# I2C-8574-cTc.net
KiCad netlist of a schematic drawn in EAGLE
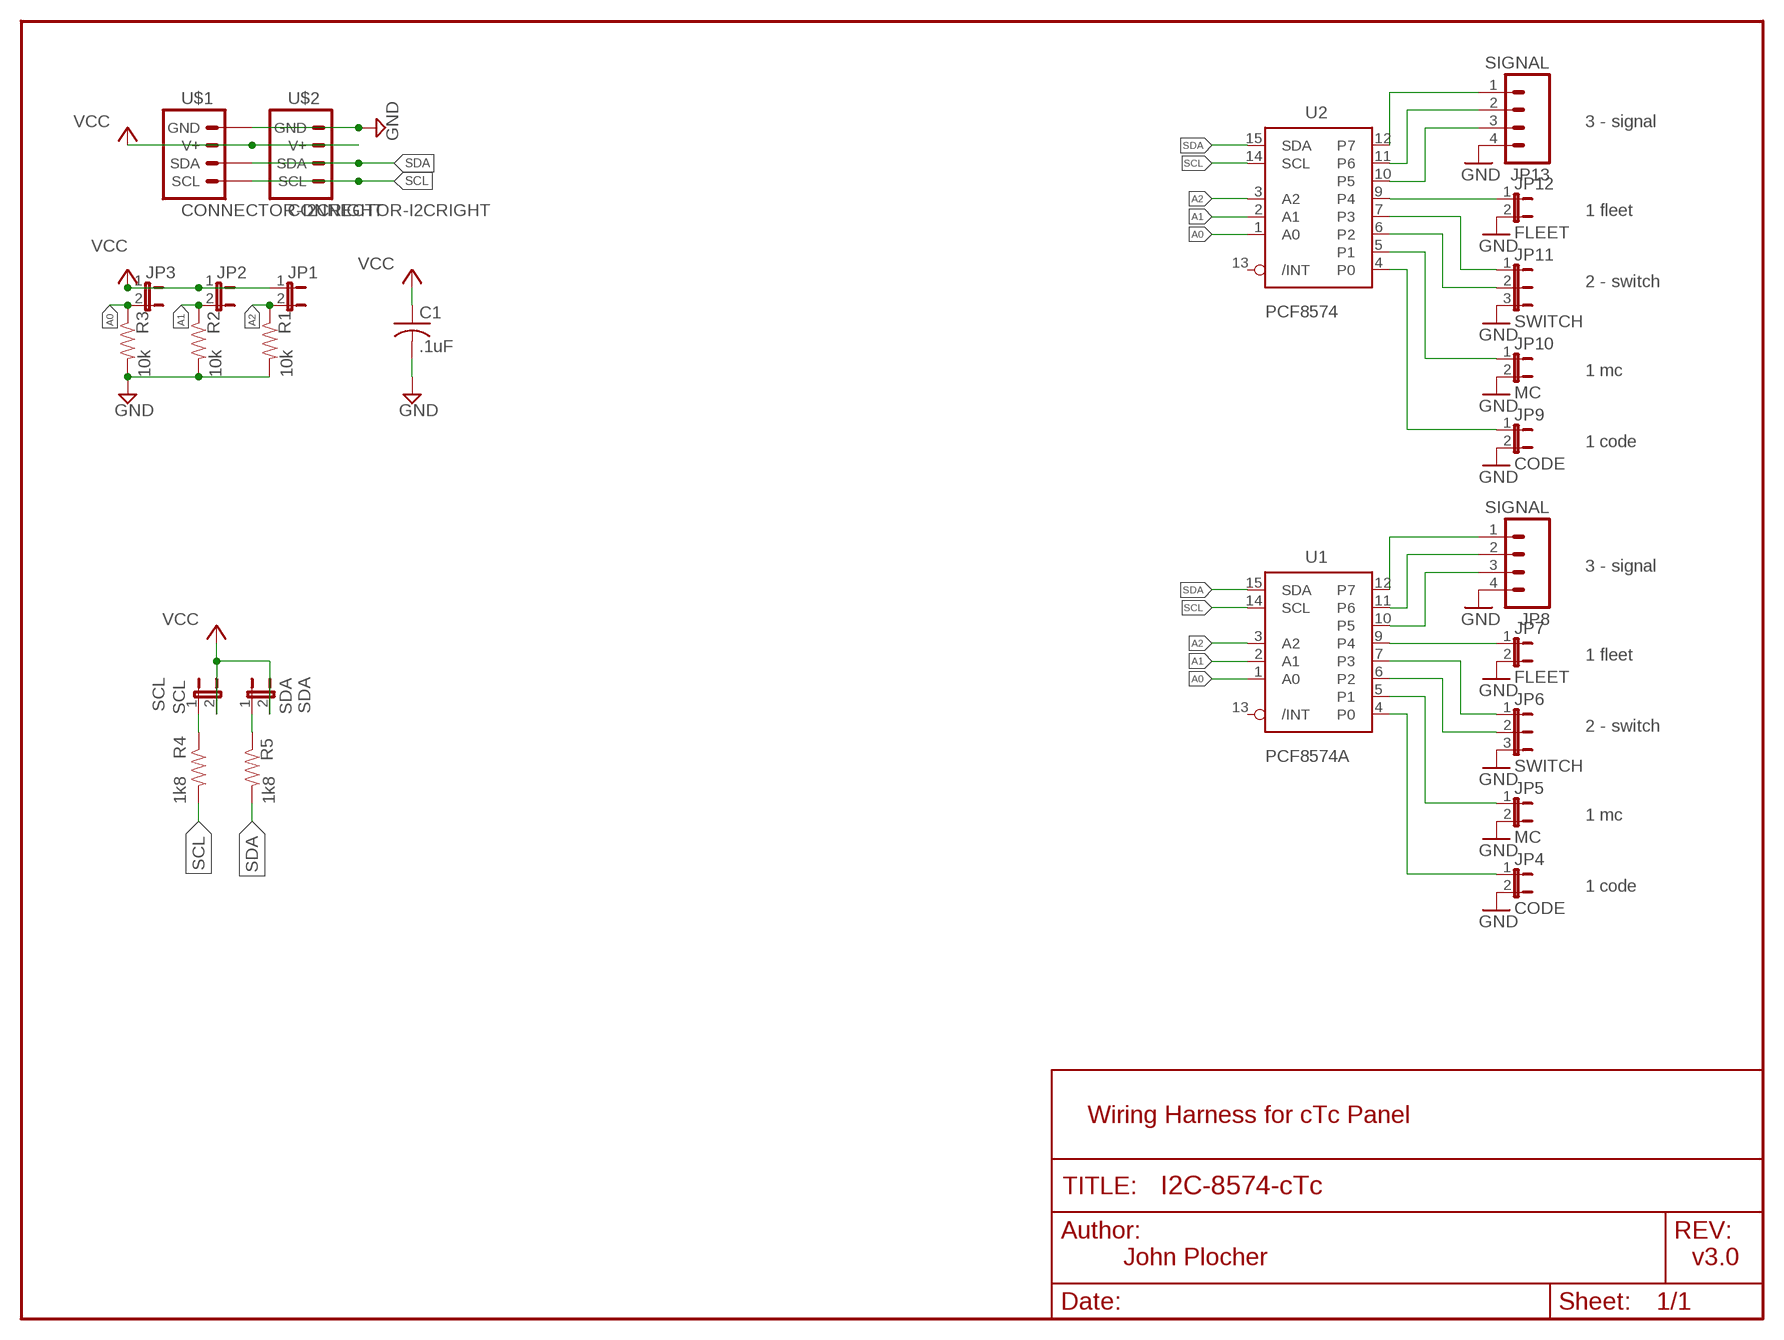
[diagram p0: schematic, sheet 1]

(export (version "E")
  (design (tool "Eeschema 10.0.6"))
  (components
    (comp (ref "C1")
      (value ".1uF")
      (footprint "eagle-import:0805-CAP")
      (libsource (lib "eagle-import") (part "CAP0805"))
    )
    (comp (ref "JP1")
      (value "JUMPER-2SMD-NO")
      (footprint "eagle-import:SJ_2S-NO")
      (libsource (lib "eagle-import") (part "JUMPER-2SMD-NO"))
    )
    (comp (ref "JP2")
      (value "JUMPER-2SMD-NO")
      (footprint "eagle-import:SJ_2S-NO")
      (libsource (lib "eagle-import") (part "JUMPER-2SMD-NO"))
    )
    (comp (ref "JP3")
      (value "JUMPER-2SMD-NO")
      (footprint "eagle-import:SJ_2S-NO")
      (libsource (lib "eagle-import") (part "JUMPER-2SMD-NO"))
    )
    (comp (ref "JP4")
      (value "CODE")
      (footprint "eagle-import:1X02_LOCK")
      (libsource (lib "eagle-import") (part "JUMPER-2PTH_LOCK"))
    )
    (comp (ref "JP5")
      (value "MC")
      (footprint "eagle-import:1X02_LOCK")
      (libsource (lib "eagle-import") (part "JUMPER-2PTH_LOCK"))
    )
    (comp (ref "JP6")
      (value "SWITCH")
      (footprint "eagle-import:1X03")
      (libsource (lib "eagle-import") (part "JUMPER-3PTH-LOCK"))
    )
    (comp (ref "JP7")
      (value "FLEET")
      (footprint "eagle-import:1X02_LOCK")
      (libsource (lib "eagle-import") (part "JUMPER-2PTH_LOCK"))
    )
    (comp (ref "JP8")
      (value "SIGNAL")
      (footprint "eagle-import:1X04_LOCK")
      (libsource (lib "eagle-import") (part "CONNECTOR-M04LOCK"))
    )
    (comp (ref "JP9")
      (value "CODE")
      (footprint "eagle-import:1X02_LOCK")
      (libsource (lib "eagle-import") (part "JUMPER-2PTH_LOCK"))
    )
    (comp (ref "JP10")
      (value "MC")
      (footprint "eagle-import:1X02_LOCK")
      (libsource (lib "eagle-import") (part "JUMPER-2PTH_LOCK"))
    )
    (comp (ref "JP11")
      (value "SWITCH")
      (footprint "eagle-import:1X03")
      (libsource (lib "eagle-import") (part "JUMPER-3PTH-LOCK"))
    )
    (comp (ref "JP12")
      (value "FLEET")
      (footprint "eagle-import:1X02_LOCK")
      (libsource (lib "eagle-import") (part "JUMPER-2PTH_LOCK"))
    )
    (comp (ref "JP13")
      (value "SIGNAL")
      (footprint "eagle-import:1X04_LOCK")
      (libsource (lib "eagle-import") (part "CONNECTOR-M04LOCK"))
    )
    (comp (ref "R1")
      (value "10k")
      (footprint "eagle-import:0805-RES")
      (libsource (lib "eagle-import") (part "R0805-RES"))
    )
    (comp (ref "R2")
      (value "10k")
      (footprint "eagle-import:0805-RES")
      (libsource (lib "eagle-import") (part "R0805-RES"))
    )
    (comp (ref "R3")
      (value "10k")
      (footprint "eagle-import:0805-RES")
      (libsource (lib "eagle-import") (part "R0805-RES"))
    )
    (comp (ref "R4")
      (value "1k8")
      (footprint "eagle-import:0805-RES")
      (libsource (lib "eagle-import") (part "R0805-RES"))
    )
    (comp (ref "R5")
      (value "1k8")
      (footprint "eagle-import:0805-RES")
      (libsource (lib "eagle-import") (part "R0805-RES"))
    )
    (comp (ref "SCL")
      (value "SCL")
      (footprint "eagle-import:1X02_LOCK")
      (libsource (lib "eagle-import") (part "JUMPER-2PTH_LOCK"))
    )
    (comp (ref "SDA")
      (value "SDA")
      (footprint "eagle-import:1X02_LOCK")
      (libsource (lib "eagle-import") (part "JUMPER-2PTH_LOCK"))
    )
    (comp (ref "U$1")
      (value "CONNECTOR-I2CRIGHT")
      (footprint "eagle-import:I2C-R")
      (libsource (lib "eagle-import") (part "CONNECTOR-I2CRIGHT"))
    )
    (comp (ref "U$2")
      (value "CONNECTOR-I2CRIGHT")
      (footprint "eagle-import:I2C-R")
      (libsource (lib "eagle-import") (part "CONNECTOR-I2CRIGHT"))
    )
    (comp (ref "U1")
      (value "PCF8574A")
      (footprint "eagle-import:SO-16DW")
      (libsource (lib "eagle-import") (part "PCF8574ADW"))
    )
    (comp (ref "U2")
      (value "PCF8574")
      (footprint "eagle-import:SO-16DW")
      (libsource (lib "eagle-import") (part "PCF8574DW"))
    )
  )
  (nets
    (net (code "1") (name "A0") (class "Default")
      (node (ref "JP3") (pin "2") (pinfunction "2_2") (pintype "passive"))
      (node (ref "R3") (pin "1") (pinfunction "1_1") (pintype "passive"))
      (node (ref "U1") (pin "1") (pinfunction "A0_1") (pintype "input"))
      (node (ref "U2") (pin "1") (pinfunction "A0_1") (pintype "input"))
    )
    (net (code "2") (name "A1") (class "Default")
      (node (ref "JP2") (pin "2") (pinfunction "2_2") (pintype "passive"))
      (node (ref "R2") (pin "1") (pinfunction "1_1") (pintype "passive"))
      (node (ref "U1") (pin "2") (pinfunction "A1_2") (pintype "input"))
      (node (ref "U2") (pin "2") (pinfunction "A1_2") (pintype "input"))
    )
    (net (code "3") (name "A2") (class "Default")
      (node (ref "JP1") (pin "2") (pinfunction "2_2") (pintype "passive"))
      (node (ref "R1") (pin "1") (pinfunction "1_1") (pintype "passive"))
      (node (ref "U1") (pin "3") (pinfunction "A2_3") (pintype "input"))
      (node (ref "U2") (pin "3") (pinfunction "A2_3") (pintype "input"))
    )
    (net (code "4") (name "GND") (class "Default")
      (node (ref "C1") (pin "2") (pinfunction "2_2") (pintype "passive"))
      (node (ref "JP10") (pin "2") (pinfunction "2_2") (pintype "passive"))
      (node (ref "JP11") (pin "3") (pinfunction "3_3") (pintype "passive"))
      (node (ref "JP12") (pin "2") (pinfunction "2_2") (pintype "passive"))
      (node (ref "JP13") (pin "4") (pinfunction "4_4") (pintype "passive"))
      (node (ref "JP4") (pin "2") (pinfunction "2_2") (pintype "passive"))
      (node (ref "JP5") (pin "2") (pinfunction "2_2") (pintype "passive"))
      (node (ref "JP6") (pin "3") (pinfunction "3_3") (pintype "passive"))
      (node (ref "JP7") (pin "2") (pinfunction "2_2") (pintype "passive"))
      (node (ref "JP8") (pin "4") (pinfunction "4_4") (pintype "passive"))
      (node (ref "JP9") (pin "2") (pinfunction "2_2") (pintype "passive"))
      (node (ref "R1") (pin "2") (pinfunction "2_2") (pintype "passive"))
      (node (ref "R2") (pin "2") (pinfunction "2_2") (pintype "passive"))
      (node (ref "R3") (pin "2") (pinfunction "2_2") (pintype "passive"))
      (node (ref "U$1") (pin "GND") (pinfunction "GND_GND") (pintype "passive"))
      (node (ref "U$1") (pin "GND@1") (pinfunction "GND_GND@1") (pintype "passive"))
      (node (ref "U$2") (pin "GND") (pinfunction "GND_GND") (pintype "passive"))
      (node (ref "U$2") (pin "GND@1") (pinfunction "GND_GND@1") (pintype "passive"))
    )
    (net (code "5") (name "Net-(R4-Pad1)") (class "Default")
      (node (ref "R4") (pin "1") (pinfunction "1_1") (pintype "passive"))
      (node (ref "SCL") (pin "1") (pinfunction "1_1") (pintype "passive"))
    )
    (net (code "6") (name "Net-(R5-Pad1)") (class "Default")
      (node (ref "R5") (pin "1") (pinfunction "1_1") (pintype "passive"))
      (node (ref "SDA") (pin "1") (pinfunction "1_1") (pintype "passive"))
    )
    (net (code "7") (name "Net-(U1B-P0)") (class "Default")
      (node (ref "JP4") (pin "1") (pinfunction "1_1") (pintype "passive"))
      (node (ref "U1") (pin "4") (pinfunction "P0_4") (pintype "bidirectional"))
    )
    (net (code "8") (name "Net-(U1B-P1)") (class "Default")
      (node (ref "JP5") (pin "1") (pinfunction "1_1") (pintype "passive"))
      (node (ref "U1") (pin "5") (pinfunction "P1_5") (pintype "bidirectional"))
    )
    (net (code "9") (name "Net-(U1B-P2)") (class "Default")
      (node (ref "JP6") (pin "2") (pinfunction "2_2") (pintype "passive"))
      (node (ref "U1") (pin "6") (pinfunction "P2_6") (pintype "bidirectional"))
    )
    (net (code "10") (name "Net-(U1B-P3)") (class "Default")
      (node (ref "JP6") (pin "1") (pinfunction "1_1") (pintype "passive"))
      (node (ref "U1") (pin "7") (pinfunction "P3_7") (pintype "bidirectional"))
    )
    (net (code "11") (name "Net-(U1B-P4)") (class "Default")
      (node (ref "JP7") (pin "1") (pinfunction "1_1") (pintype "passive"))
      (node (ref "U1") (pin "9") (pinfunction "P4_9") (pintype "bidirectional"))
    )
    (net (code "12") (name "Net-(U1B-P5)") (class "Default")
      (node (ref "JP8") (pin "3") (pinfunction "3_3") (pintype "passive"))
      (node (ref "U1") (pin "10") (pinfunction "P5_10") (pintype "bidirectional"))
    )
    (net (code "13") (name "Net-(U1B-P6)") (class "Default")
      (node (ref "JP8") (pin "2") (pinfunction "2_2") (pintype "passive"))
      (node (ref "U1") (pin "11") (pinfunction "P6_11") (pintype "bidirectional"))
    )
    (net (code "14") (name "Net-(U1B-P7)") (class "Default")
      (node (ref "JP8") (pin "1") (pinfunction "1_1") (pintype "passive"))
      (node (ref "U1") (pin "12") (pinfunction "P7_12") (pintype "bidirectional"))
    )
    (net (code "15") (name "Net-(U2B-P0)") (class "Default")
      (node (ref "JP9") (pin "1") (pinfunction "1_1") (pintype "passive"))
      (node (ref "U2") (pin "4") (pinfunction "P0_4") (pintype "bidirectional"))
    )
    (net (code "16") (name "Net-(U2B-P1)") (class "Default")
      (node (ref "JP10") (pin "1") (pinfunction "1_1") (pintype "passive"))
      (node (ref "U2") (pin "5") (pinfunction "P1_5") (pintype "bidirectional"))
    )
    (net (code "17") (name "Net-(U2B-P2)") (class "Default")
      (node (ref "JP11") (pin "2") (pinfunction "2_2") (pintype "passive"))
      (node (ref "U2") (pin "6") (pinfunction "P2_6") (pintype "bidirectional"))
    )
    (net (code "18") (name "Net-(U2B-P3)") (class "Default")
      (node (ref "JP11") (pin "1") (pinfunction "1_1") (pintype "passive"))
      (node (ref "U2") (pin "7") (pinfunction "P3_7") (pintype "bidirectional"))
    )
    (net (code "19") (name "Net-(U2B-P4)") (class "Default")
      (node (ref "JP12") (pin "1") (pinfunction "1_1") (pintype "passive"))
      (node (ref "U2") (pin "9") (pinfunction "P4_9") (pintype "bidirectional"))
    )
    (net (code "20") (name "Net-(U2B-P5)") (class "Default")
      (node (ref "JP13") (pin "3") (pinfunction "3_3") (pintype "passive"))
      (node (ref "U2") (pin "10") (pinfunction "P5_10") (pintype "bidirectional"))
    )
    (net (code "21") (name "Net-(U2B-P6)") (class "Default")
      (node (ref "JP13") (pin "2") (pinfunction "2_2") (pintype "passive"))
      (node (ref "U2") (pin "11") (pinfunction "P6_11") (pintype "bidirectional"))
    )
    (net (code "22") (name "Net-(U2B-P7)") (class "Default")
      (node (ref "JP13") (pin "1") (pinfunction "1_1") (pintype "passive"))
      (node (ref "U2") (pin "12") (pinfunction "P7_12") (pintype "bidirectional"))
    )
    (net (code "23") (name "SCL") (class "Default")
      (node (ref "R4") (pin "2") (pinfunction "2_2") (pintype "passive"))
      (node (ref "U$1") (pin "SCL") (pinfunction "SCL_SCL") (pintype "passive"))
      (node (ref "U$1") (pin "SCL@1") (pinfunction "SCL_SCL@1") (pintype "passive"))
      (node (ref "U$2") (pin "SCL") (pinfunction "SCL_SCL") (pintype "passive"))
      (node (ref "U$2") (pin "SCL@1") (pinfunction "SCL_SCL@1") (pintype "passive"))
      (node (ref "U1") (pin "14") (pinfunction "SCL_14") (pintype "input"))
      (node (ref "U2") (pin "14") (pinfunction "SCL_14") (pintype "input"))
    )
    (net (code "24") (name "SDA") (class "Default")
      (node (ref "R5") (pin "2") (pinfunction "2_2") (pintype "passive"))
      (node (ref "U$1") (pin "SDA") (pinfunction "SDA_SDA") (pintype "passive"))
      (node (ref "U$1") (pin "SDA@1") (pinfunction "SDA_SDA@1") (pintype "passive"))
      (node (ref "U$2") (pin "SDA") (pinfunction "SDA_SDA") (pintype "passive"))
      (node (ref "U$2") (pin "SDA@1") (pinfunction "SDA_SDA@1") (pintype "passive"))
      (node (ref "U1") (pin "15") (pinfunction "SDA_15") (pintype "bidirectional"))
      (node (ref "U2") (pin "15") (pinfunction "SDA_15") (pintype "bidirectional"))
    )
    (net (code "25") (name "VCC") (class "Default")
      (node (ref "C1") (pin "1") (pinfunction "1_1") (pintype "passive"))
      (node (ref "JP1") (pin "1") (pinfunction "1_1") (pintype "passive"))
      (node (ref "JP2") (pin "1") (pinfunction "1_1") (pintype "passive"))
      (node (ref "JP3") (pin "1") (pinfunction "1_1") (pintype "passive"))
      (node (ref "SCL") (pin "2") (pinfunction "2_2") (pintype "passive"))
      (node (ref "SDA") (pin "2") (pinfunction "2_2") (pintype "passive"))
      (node (ref "U$1") (pin "V+") (pinfunction "V+_V+") (pintype "passive"))
      (node (ref "U$1") (pin "V+@1") (pinfunction "V+_V+@1") (pintype "passive"))
      (node (ref "U$2") (pin "V+") (pinfunction "V+_V+") (pintype "passive"))
      (node (ref "U$2") (pin "V+@1") (pinfunction "V+_V+@1") (pintype "passive"))
    )
    (net (code "26") (name "unconnected-(U1B-{slash}INT-Pad13)") (class "Default")
      (node (ref "U1") (pin "13") (pinfunction "/INT_13") (pintype "output"))
    )
    (net (code "27") (name "unconnected-(U2B-{slash}INT-Pad13)") (class "Default")
      (node (ref "U2") (pin "13") (pinfunction "/INT_13") (pintype "output"))
    )
  )
)
